# Spinning.net
KiCad netlist of a schematic drawn in EAGLE
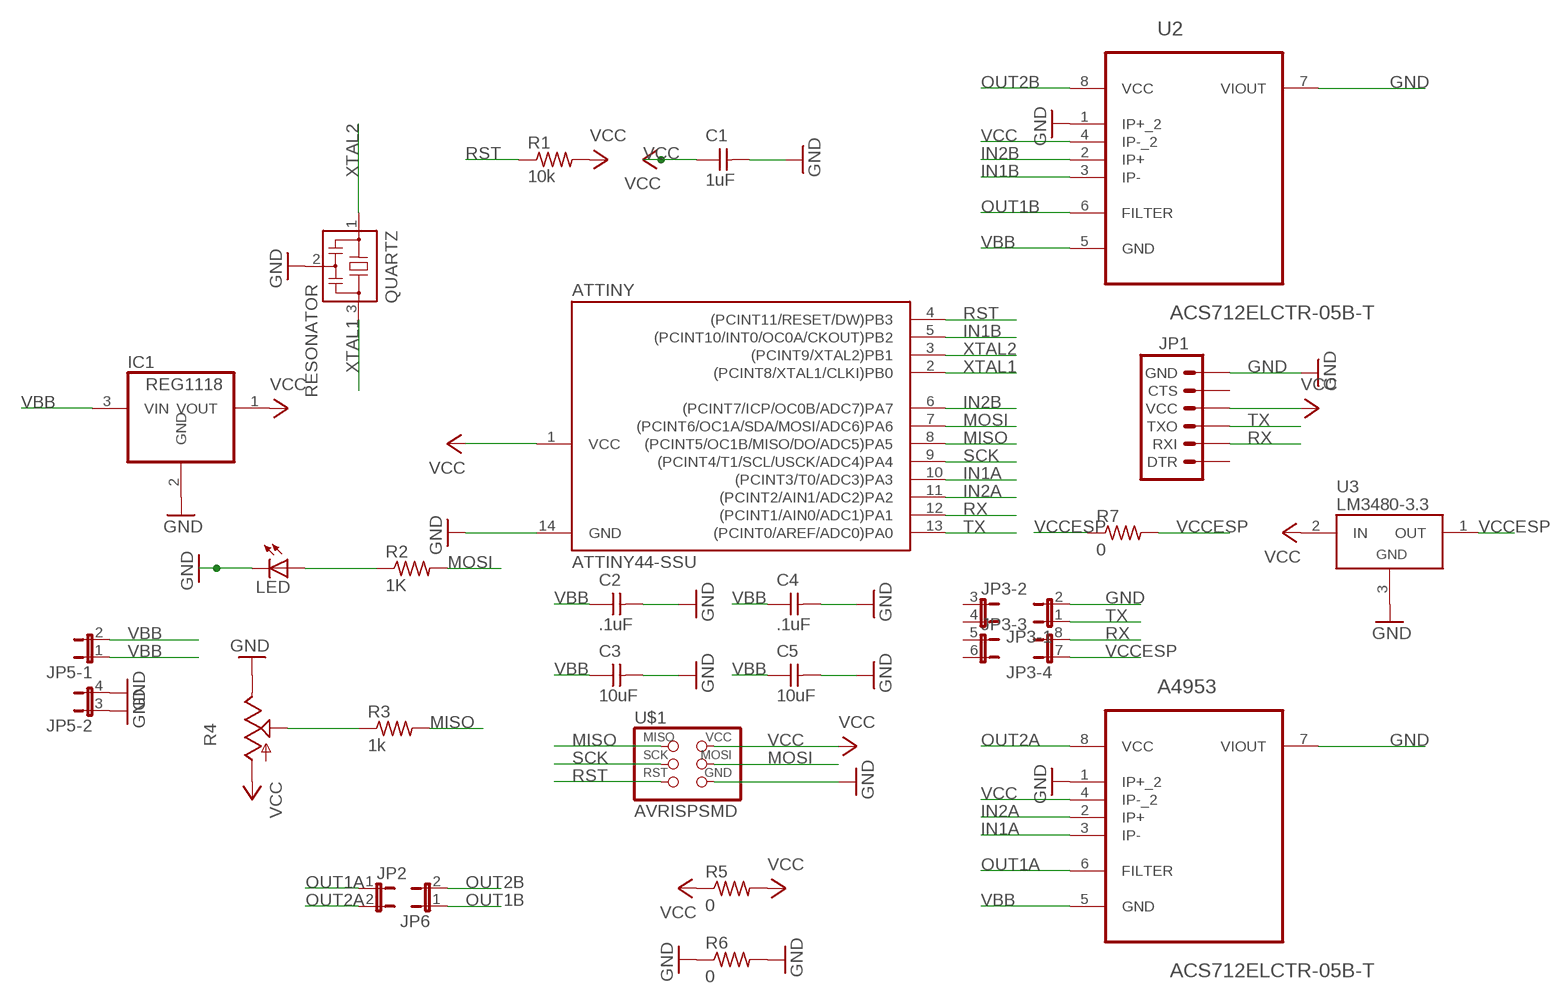
[diagram p0: schematic, sheet 1]

(export (version "E")
  (design (tool "Eeschema 10.0.6"))
  (components
    (comp (ref "A4953")
      (value "ACS712ELCTR-05B-T")
      (footprint "eagle-import:SOIC127P600X175-8N")
      (libsource (lib "eagle-import") (part "ACS712ELCTR-05B-T"))
    )
    (comp (ref "ATTINY")
      (value "ATTINY44-SSU")
      (footprint "eagle-import:SOIC14")
      (libsource (lib "eagle-import") (part "ATTINY44-SSU"))
    )
    (comp (ref "C1")
      (value "1uF")
      (footprint "eagle-import:1206")
      (libsource (lib "eagle-import") (part "UNPOLARIZED_CAPACITOR1206"))
    )
    (comp (ref "C2")
      (value ".1uF")
      (footprint "eagle-import:1206")
      (libsource (lib "eagle-import") (part "UNPOLARIZED_CAPACITOR1206"))
    )
    (comp (ref "C3")
      (value "10uF")
      (footprint "eagle-import:1206")
      (libsource (lib "eagle-import") (part "UNPOLARIZED_CAPACITOR1206"))
    )
    (comp (ref "C4")
      (value ".1uF")
      (footprint "eagle-import:1206")
      (libsource (lib "eagle-import") (part "UNPOLARIZED_CAPACITOR1206"))
    )
    (comp (ref "C5")
      (value "10uF")
      (footprint "eagle-import:1206")
      (libsource (lib "eagle-import") (part "UNPOLARIZED_CAPACITOR1206"))
    )
    (comp (ref "IC1")
      (value "REG1118")
      (footprint "eagle-import:SOT223")
      (fields (field (name "MPN") "REG1118-2.85/2K5G4"))
      (libsource (lib "eagle-import") (part "REG1118"))
    )
    (comp (ref "JP1")
      (value "ARDUINO_SERIAL_PROGRAMLONGPADS")
      (footprint "eagle-import:1X06_LONGPADS")
      (libsource (lib "eagle-import") (part "ARDUINO_SERIAL_PROGRAMLONGPADS"))
    )
    (comp (ref "JP2")
      (value "JP1E")
      (footprint "eagle-import:JP1")
      (libsource (lib "eagle-import") (part "JP1E"))
    )
    (comp (ref "JP3")
      (value "JP4QE")
      (footprint "eagle-import:JP4Q")
      (libsource (lib "eagle-import") (part "JP4QE"))
    )
    (comp (ref "JP5")
      (value "JP2QE")
      (footprint "eagle-import:JP2Q")
      (libsource (lib "eagle-import") (part "JP2QE"))
    )
    (comp (ref "JP6")
      (value "JP1E")
      (footprint "eagle-import:JP1")
      (libsource (lib "eagle-import") (part "JP1E"))
    )
    (comp (ref "LED")
      (value "LED1206")
      (footprint "eagle-import:1206")
      (libsource (lib "eagle-import") (part "LED1206"))
    )
    (comp (ref "QUARTZ")
      (value "RESONATOR")
      (footprint "eagle-import:EFOBM")
      (libsource (lib "eagle-import") (part "RESONATOR"))
    )
    (comp (ref "R1")
      (value "10k")
      (footprint "eagle-import:1206")
      (libsource (lib "eagle-import") (part "RESISTOR1206"))
    )
    (comp (ref "R2")
      (value "1K")
      (footprint "eagle-import:1206")
      (libsource (lib "eagle-import") (part "RESISTOR1206"))
    )
    (comp (ref "R3")
      (value "1k")
      (footprint "eagle-import:1206")
      (libsource (lib "eagle-import") (part "RESISTOR1206"))
    )
    (comp (ref "R4")
      (value "TRIM_US-CIP20C-6MM")
      (footprint "eagle-import:CIP20C-6MM")
      (libsource (lib "eagle-import") (part "TRIM_US-CIP20C-6MM"))
    )
    (comp (ref "R5")
      (value "0")
      (footprint "eagle-import:1206")
      (libsource (lib "eagle-import") (part "RESISTOR1206"))
    )
    (comp (ref "R6")
      (value "0")
      (footprint "eagle-import:1206")
      (libsource (lib "eagle-import") (part "RESISTOR1206"))
    )
    (comp (ref "R7")
      (value "0")
      (footprint "eagle-import:1206")
      (libsource (lib "eagle-import") (part "RESISTOR1206"))
    )
    (comp (ref "U$1")
      (value "AVRISPSMD")
      (footprint "eagle-import:2X03SMD")
      (libsource (lib "eagle-import") (part "AVRISPSMD"))
    )
    (comp (ref "U2")
      (value "ACS712ELCTR-05B-T")
      (footprint "eagle-import:SOIC127P600X175-8N")
      (libsource (lib "eagle-import") (part "ACS712ELCTR-05B-T"))
    )
    (comp (ref "U3")
      (value "LM3480-3.3")
      (footprint "eagle-import:SOT-23-3")
      (libsource (lib "eagle-import") (part "LM3480-3.3"))
    )
  )
  (nets
    (net (code "1") (name "/IN1A") (class "Default")
      (node (ref "A4953") (pin "3") (pinfunction "IP-_3") (pintype "input"))
      (node (ref "ATTINY") (pin "10") (pinfunction "(PCINT3/T0/ADC3)PA3_10") (pintype "bidirectional"))
    )
    (net (code "2") (name "/IN1B") (class "Default")
      (node (ref "ATTINY") (pin "5") (pinfunction "(PCINT10/INT0/OC0A/CKOUT)PB2_5") (pintype "bidirectional"))
      (node (ref "U2") (pin "3") (pinfunction "IP-_3") (pintype "input"))
    )
    (net (code "3") (name "/IN2A") (class "Default")
      (node (ref "A4953") (pin "2") (pinfunction "IP+_2") (pintype "input"))
      (node (ref "ATTINY") (pin "11") (pinfunction "(PCINT2/AIN1/ADC2)PA2_11") (pintype "bidirectional"))
    )
    (net (code "4") (name "/IN2B") (class "Default")
      (node (ref "ATTINY") (pin "6") (pinfunction "(PCINT7/ICP/OC0B/ADC7)PA7_6") (pintype "bidirectional"))
      (node (ref "U2") (pin "2") (pinfunction "IP+_2") (pintype "input"))
    )
    (net (code "5") (name "/MISO") (class "Default")
      (node (ref "ATTINY") (pin "8") (pinfunction "(PCINT5/OC1B/MISO/DO/ADC5)PA5_8") (pintype "bidirectional"))
      (node (ref "R3") (pin "2") (pinfunction "2_2") (pintype "passive"))
      (node (ref "U$1") (pin "1") (pinfunction "MISO_1") (pintype "passive"))
    )
    (net (code "6") (name "/MOSI") (class "Default")
      (node (ref "ATTINY") (pin "7") (pinfunction "(PCINT6/OC1A/SDA/MOSI/ADC6)PA6_7") (pintype "bidirectional"))
      (node (ref "R2") (pin "2") (pinfunction "2_2") (pintype "passive"))
      (node (ref "U$1") (pin "4") (pinfunction "MOSI_4") (pintype "passive"))
    )
    (net (code "7") (name "/OUT1A") (class "Default")
      (node (ref "A4953") (pin "6") (pinfunction "FILTER_6") (pintype "input"))
      (node (ref "JP2") (pin "1") (pinfunction "1_1") (pintype "passive"))
    )
    (net (code "8") (name "/OUT1B") (class "Default")
      (node (ref "JP6") (pin "1") (pinfunction "1_1") (pintype "passive"))
      (node (ref "U2") (pin "6") (pinfunction "FILTER_6") (pintype "input"))
    )
    (net (code "9") (name "/OUT2A") (class "Default")
      (node (ref "A4953") (pin "8") (pinfunction "VCC_8") (pintype "power_in"))
      (node (ref "JP2") (pin "2") (pinfunction "2_2") (pintype "passive"))
    )
    (net (code "10") (name "/OUT2B") (class "Default")
      (node (ref "JP6") (pin "2") (pinfunction "2_2") (pintype "passive"))
      (node (ref "U2") (pin "8") (pinfunction "VCC_8") (pintype "power_in"))
    )
    (net (code "11") (name "/RST") (class "Default")
      (node (ref "ATTINY") (pin "4") (pinfunction "(PCINT11/RESET/DW)PB3_4") (pintype "bidirectional"))
      (node (ref "R1") (pin "1") (pinfunction "1_1") (pintype "passive"))
      (node (ref "U$1") (pin "5") (pinfunction "RST_5") (pintype "passive"))
    )
    (net (code "12") (name "/RX") (class "Default")
      (node (ref "ATTINY") (pin "12") (pinfunction "(PCINT1/AIN0/ADC1)PA1_12") (pintype "bidirectional"))
      (node (ref "JP1") (pin "2") (pinfunction "RXI_2") (pintype "passive"))
      (node (ref "JP3") (pin "8") (pinfunction "2_8") (pintype "passive"))
    )
    (net (code "13") (name "/SCK") (class "Default")
      (node (ref "ATTINY") (pin "9") (pinfunction "(PCINT4/T1/SCL/USCK/ADC4)PA4_9") (pintype "bidirectional"))
      (node (ref "U$1") (pin "3") (pinfunction "SCK_3") (pintype "passive"))
    )
    (net (code "14") (name "/TX") (class "Default")
      (node (ref "ATTINY") (pin "13") (pinfunction "(PCINT0/AREF/ADC0)PA0_13") (pintype "bidirectional"))
      (node (ref "JP1") (pin "3") (pinfunction "TXO_3") (pintype "passive"))
      (node (ref "JP3") (pin "1") (pinfunction "1_1") (pintype "passive"))
    )
    (net (code "15") (name "/VBB") (class "Default")
      (node (ref "A4953") (pin "5") (pinfunction "GND_5") (pintype "passive"))
      (node (ref "C2") (pin "1") (pinfunction "1_1") (pintype "passive"))
      (node (ref "C3") (pin "1") (pinfunction "1_1") (pintype "passive"))
      (node (ref "C4") (pin "1") (pinfunction "1_1") (pintype "passive"))
      (node (ref "C5") (pin "1") (pinfunction "1_1") (pintype "passive"))
      (node (ref "IC1") (pin "3") (pinfunction "VIN_3") (pintype "input"))
      (node (ref "JP5") (pin "1") (pinfunction "1_1") (pintype "passive"))
      (node (ref "JP5") (pin "2") (pinfunction "2_2") (pintype "passive"))
      (node (ref "U2") (pin "5") (pinfunction "GND_5") (pintype "passive"))
    )
    (net (code "16") (name "/VCCESP") (class "Default")
      (node (ref "JP3") (pin "7") (pinfunction "1_7") (pintype "passive"))
      (node (ref "R7") (pin "1") (pinfunction "1_1") (pintype "passive"))
      (node (ref "R7") (pin "2") (pinfunction "2_2") (pintype "passive"))
      (node (ref "U3") (pin "1") (pinfunction "OUT_1") (pintype "power_in"))
    )
    (net (code "17") (name "/XTAL1") (class "Default")
      (node (ref "ATTINY") (pin "2") (pinfunction "(PCINT8/XTAL1/CLKI)PB0_2") (pintype "bidirectional"))
      (node (ref "QUARTZ") (pin "3") (pinfunction "3_3") (pintype "passive"))
    )
    (net (code "18") (name "/XTAL2") (class "Default")
      (node (ref "ATTINY") (pin "3") (pinfunction "(PCINT9/XTAL2)PB1_3") (pintype "bidirectional"))
      (node (ref "QUARTZ") (pin "1") (pinfunction "1_1") (pintype "passive"))
    )
    (net (code "19") (name "GND") (class "Default")
      (node (ref "A4953") (pin "1") (pinfunction "IP+_2_1") (pintype "input"))
      (node (ref "A4953") (pin "7") (pinfunction "VIOUT_7") (pintype "output"))
      (node (ref "ATTINY") (pin "14") (pinfunction "GND_14") (pintype "power_in"))
      (node (ref "C1") (pin "2") (pinfunction "2_2") (pintype "passive"))
      (node (ref "C2") (pin "2") (pinfunction "2_2") (pintype "passive"))
      (node (ref "C3") (pin "2") (pinfunction "2_2") (pintype "passive"))
      (node (ref "C4") (pin "2") (pinfunction "2_2") (pintype "passive"))
      (node (ref "C5") (pin "2") (pinfunction "2_2") (pintype "passive"))
      (node (ref "IC1") (pin "2") (pinfunction "GND_2") (pintype "power_in"))
      (node (ref "JP1") (pin "6") (pinfunction "GND_6") (pintype "passive"))
      (node (ref "JP3") (pin "2") (pinfunction "2_2") (pintype "passive"))
      (node (ref "JP5") (pin "3") (pinfunction "1_3") (pintype "passive"))
      (node (ref "JP5") (pin "4") (pinfunction "2_4") (pintype "passive"))
      (node (ref "LED") (pin "2") (pinfunction "C_2") (pintype "passive"))
      (node (ref "QUARTZ") (pin "2") (pinfunction "2_2") (pintype "passive"))
      (node (ref "R4") (pin "E") (pinfunction "E_E") (pintype "passive"))
      (node (ref "R6") (pin "1") (pinfunction "1_1") (pintype "passive"))
      (node (ref "R6") (pin "2") (pinfunction "2_2") (pintype "passive"))
      (node (ref "U$1") (pin "6") (pinfunction "GND_6") (pintype "passive"))
      (node (ref "U2") (pin "1") (pinfunction "IP+_2_1") (pintype "input"))
      (node (ref "U2") (pin "7") (pinfunction "VIOUT_7") (pintype "output"))
      (node (ref "U3") (pin "3") (pinfunction "GND_3") (pintype "power_in"))
    )
    (net (code "20") (name "Net-(LED-A)") (class "Default")
      (node (ref "LED") (pin "1") (pinfunction "A_1") (pintype "passive"))
      (node (ref "R2") (pin "1") (pinfunction "1_1") (pintype "passive"))
    )
    (net (code "21") (name "Net-(R3-Pad1)") (class "Default")
      (node (ref "R3") (pin "1") (pinfunction "1_1") (pintype "passive"))
      (node (ref "R4") (pin "S") (pinfunction "S_S") (pintype "passive"))
    )
    (net (code "22") (name "VCC") (class "Default")
      (node (ref "A4953") (pin "4") (pinfunction "IP-_2_4") (pintype "input"))
      (node (ref "ATTINY") (pin "1") (pinfunction "VCC_1") (pintype "power_in"))
      (node (ref "C1") (pin "1") (pinfunction "1_1") (pintype "passive"))
      (node (ref "IC1") (pin "1") (pinfunction "VOUT_1") (pintype "output"))
      (node (ref "JP1") (pin "4") (pinfunction "VCC_4") (pintype "passive"))
      (node (ref "R1") (pin "2") (pinfunction "2_2") (pintype "passive"))
      (node (ref "R4") (pin "A") (pinfunction "A_A") (pintype "passive"))
      (node (ref "R5") (pin "1") (pinfunction "1_1") (pintype "passive"))
      (node (ref "R5") (pin "2") (pinfunction "2_2") (pintype "passive"))
      (node (ref "U$1") (pin "2") (pinfunction "VCC_2") (pintype "passive"))
      (node (ref "U2") (pin "4") (pinfunction "IP-_2_4") (pintype "input"))
      (node (ref "U3") (pin "2") (pinfunction "IN_2") (pintype "power_in"))
    )
    (net (code "23") (name "unconnected-(JP1-CTS-Pad5)") (class "Default")
      (node (ref "JP1") (pin "5") (pinfunction "CTS_5") (pintype "passive"))
    )
    (net (code "24") (name "unconnected-(JP1-DTR-Pad1)") (class "Default")
      (node (ref "JP1") (pin "1") (pinfunction "DTR_1") (pintype "passive"))
    )
    (net (code "25") (name "unconnected-(JP3B-1-Pad3)") (class "Default")
      (node (ref "JP3") (pin "3") (pinfunction "1_3") (pintype "passive"))
    )
    (net (code "26") (name "unconnected-(JP3B-2-Pad4)") (class "Default")
      (node (ref "JP3") (pin "4") (pinfunction "2_4") (pintype "passive"))
    )
    (net (code "27") (name "unconnected-(JP3C-1-Pad5)") (class "Default")
      (node (ref "JP3") (pin "5") (pinfunction "1_5") (pintype "passive"))
    )
    (net (code "28") (name "unconnected-(JP3C-2-Pad6)") (class "Default")
      (node (ref "JP3") (pin "6") (pinfunction "2_6") (pintype "passive"))
    )
  )
)
